# Cree_4x4__Led_Panel_V3.net
KiCad netlist of a schematic drawn in EAGLE
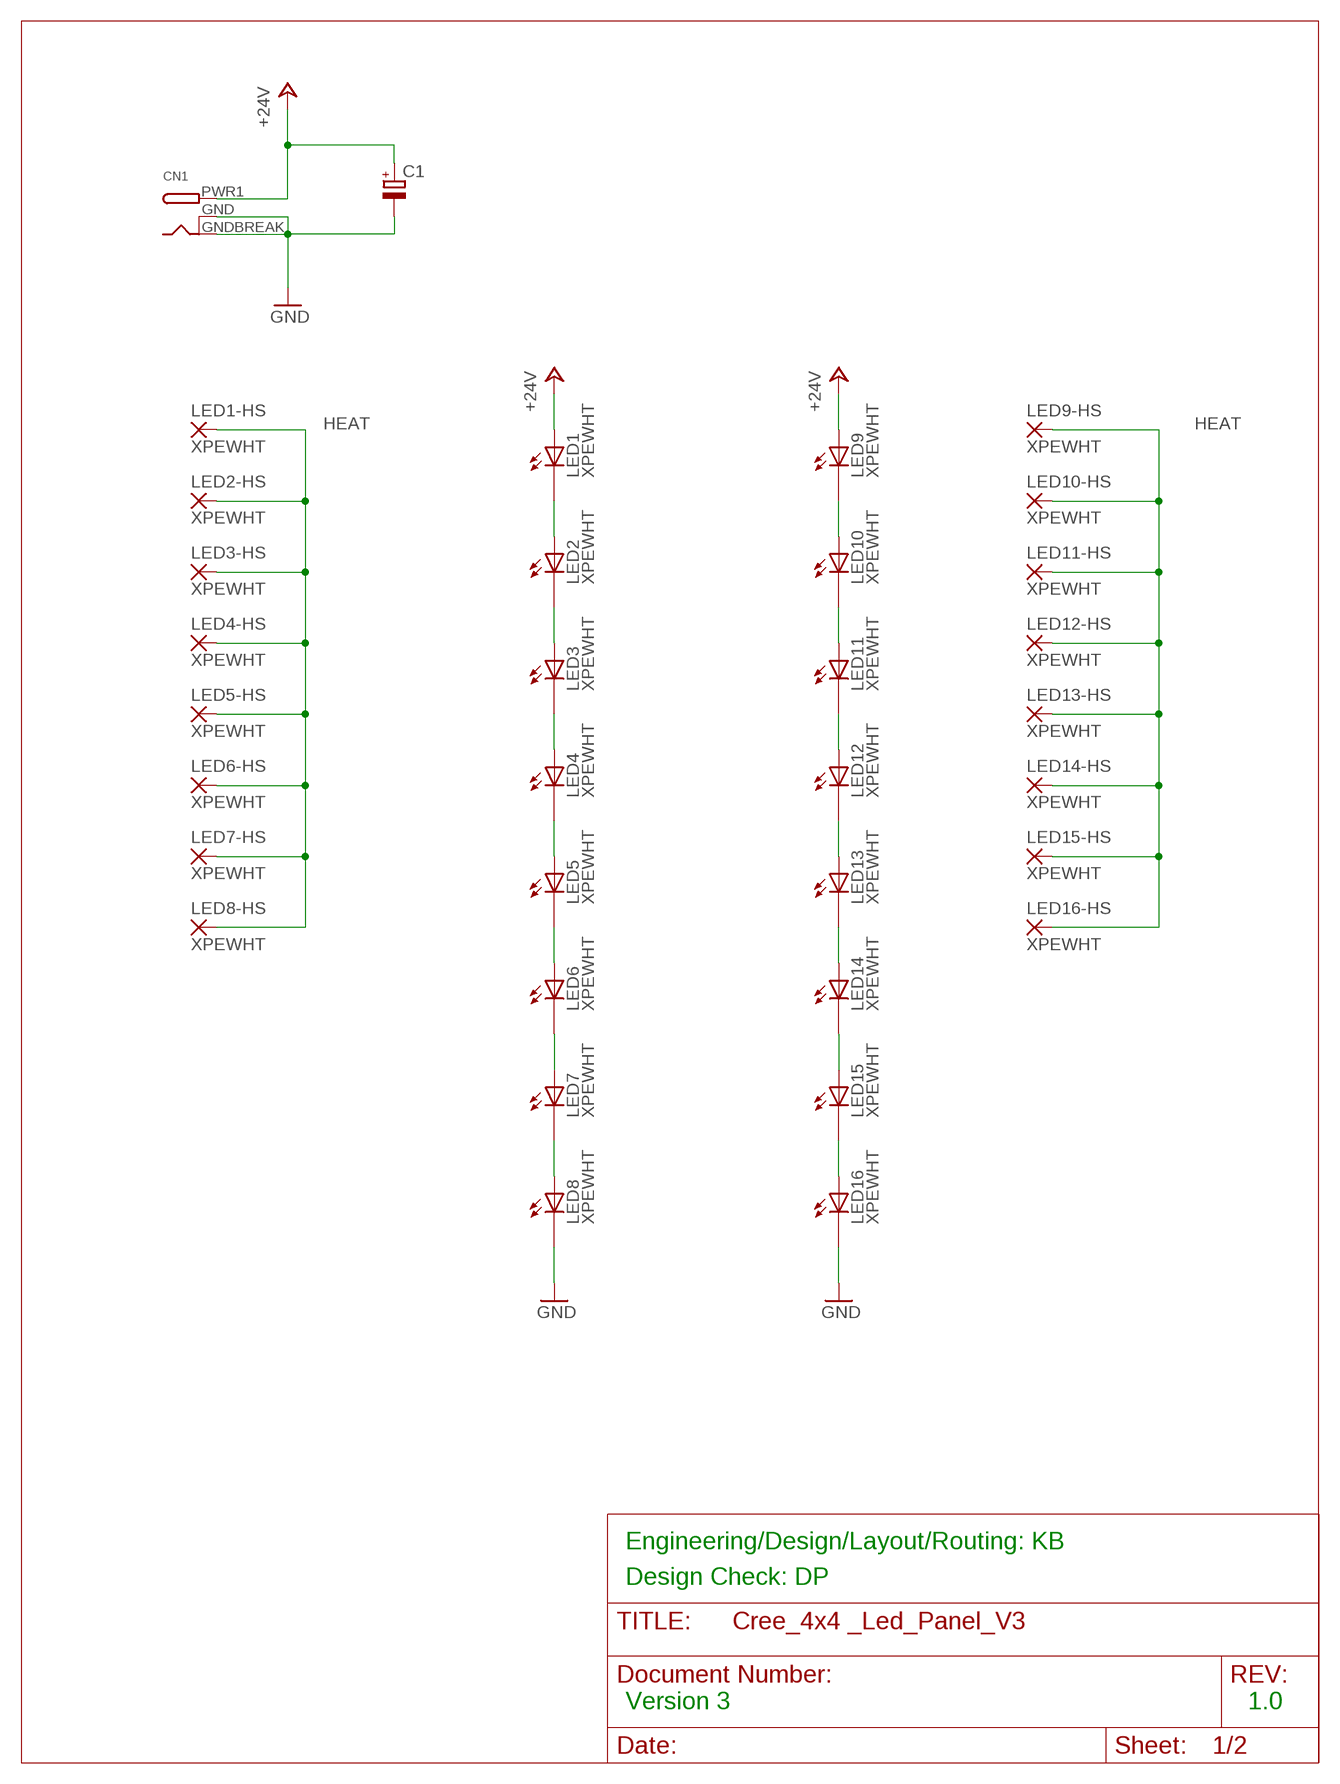
[diagram p0: schematic, sheet 1]
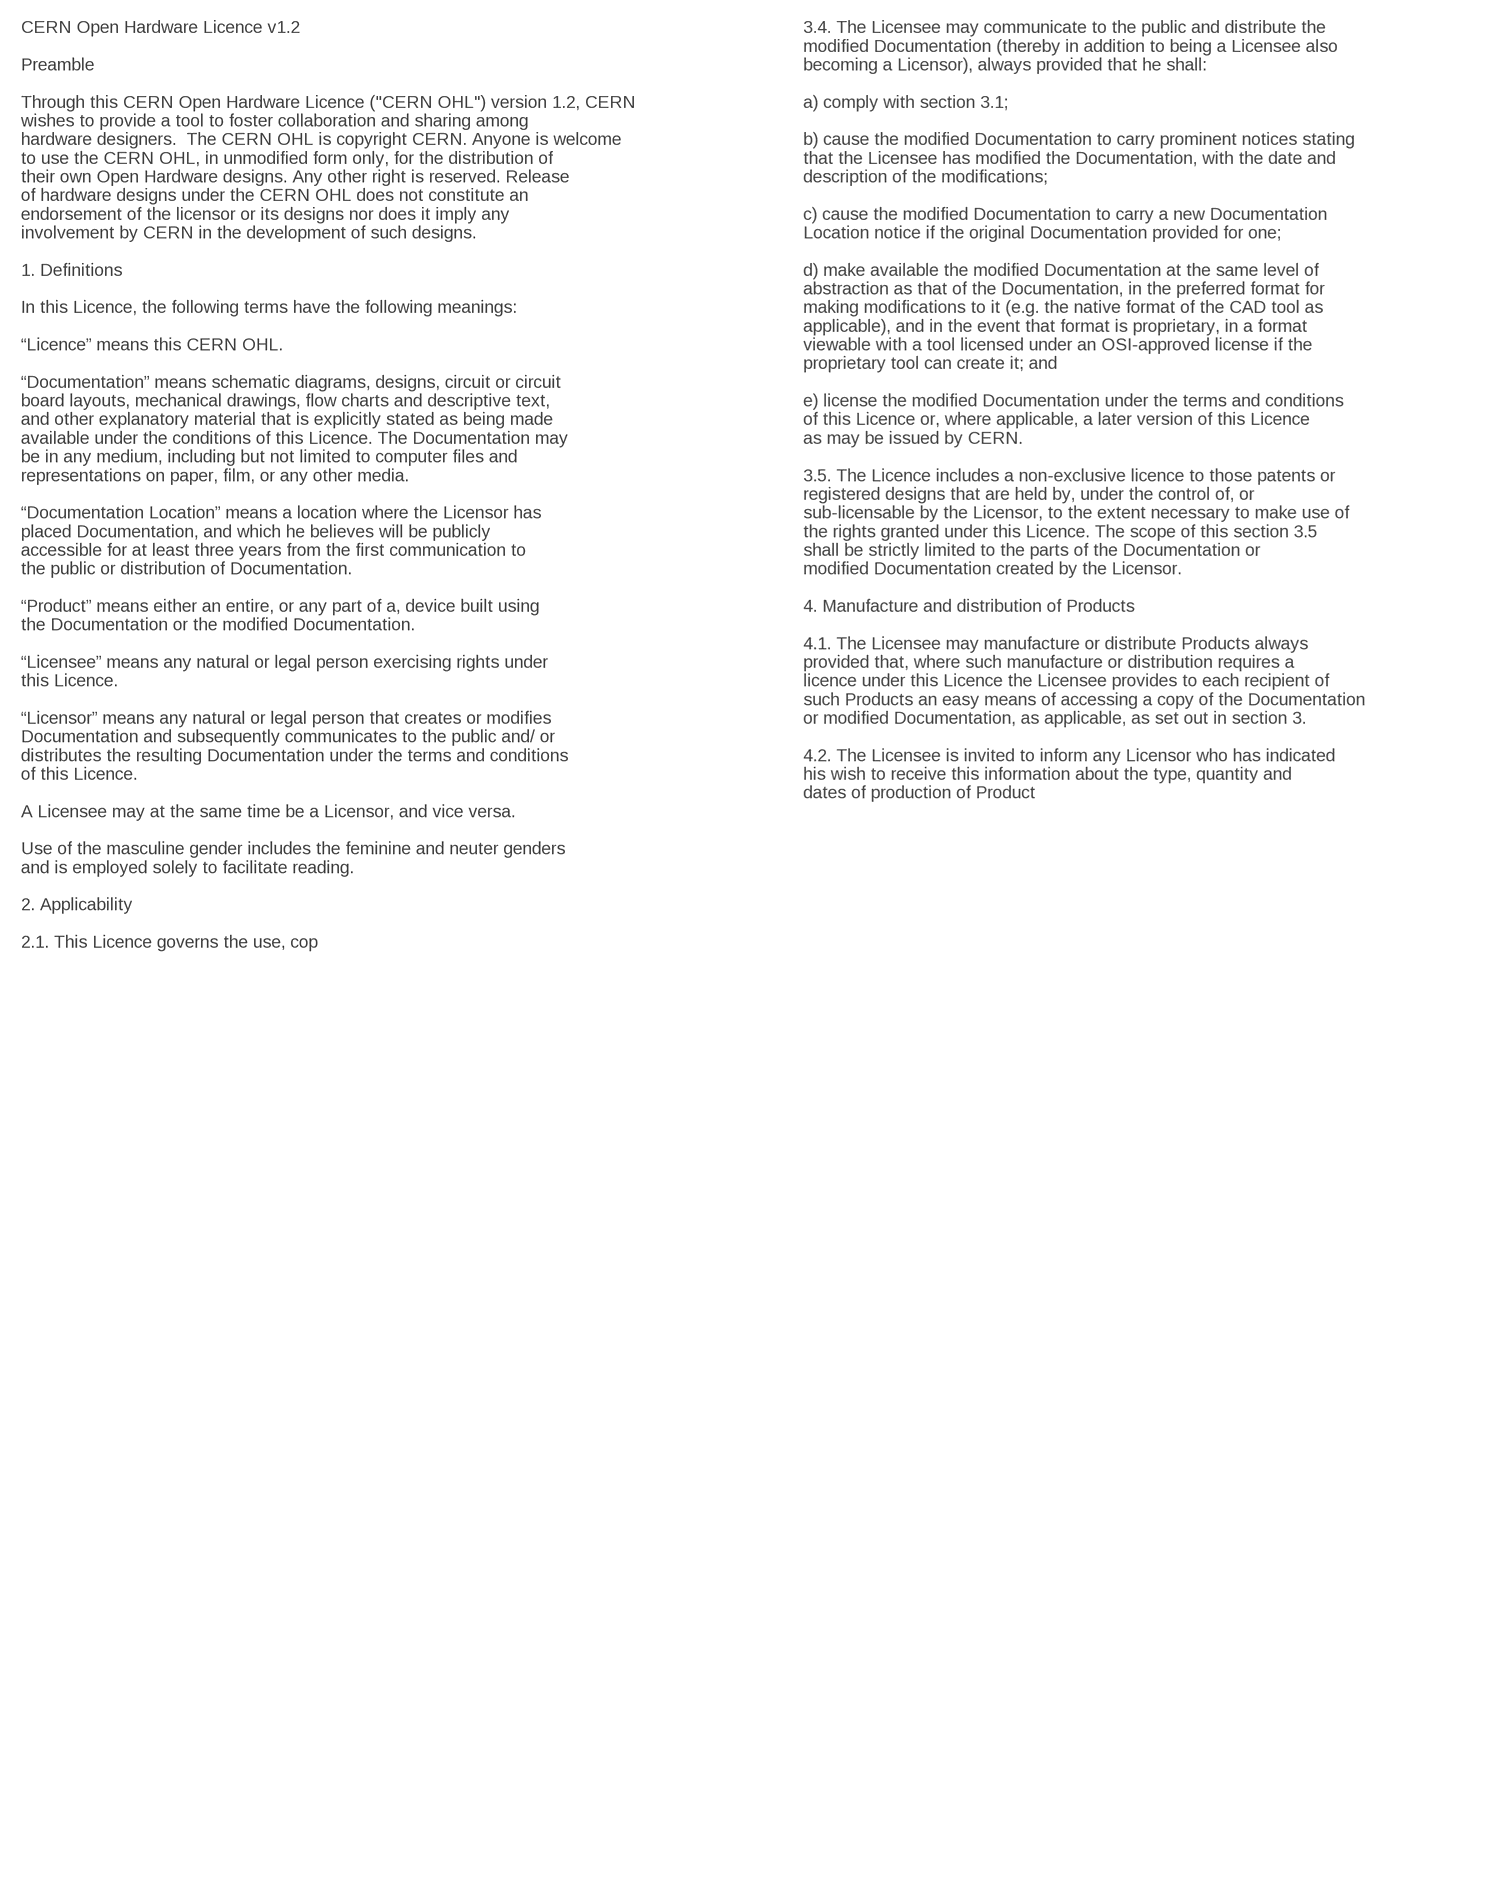
[diagram p1: schematic, sheet 2]

(export (version "E")
  (design (tool "Eeschema 10.0.6"))
  (components
    (comp (ref "C1")
      (value "CPOL-EUSMCC")
      (footprint "eagle-import:SMC_C")
      (libsource (lib "eagle-import") (part "CPOL-EUSMCC"))
    )
    (comp (ref "CN1")
      (value "DCBARRELSMT")
      (footprint "eagle-import:DCJACK_2MM_SMT")
      (libsource (lib "eagle-import") (part "DCBARRELSMT"))
    )
    (comp (ref "LED1")
      (value "XPEWHT")
      (footprint "eagle-import:CREE_XLAMP")
      (libsource (lib "eagle-import") (part "XPEWHT-01-0000-00BC2"))
    )
    (comp (ref "LED2")
      (value "XPEWHT")
      (footprint "eagle-import:CREE_XLAMP")
      (libsource (lib "eagle-import") (part "XPEWHT-01-0000-00BC2"))
    )
    (comp (ref "LED3")
      (value "XPEWHT")
      (footprint "eagle-import:CREE_XLAMP")
      (libsource (lib "eagle-import") (part "XPEWHT-01-0000-00BC2"))
    )
    (comp (ref "LED4")
      (value "XPEWHT")
      (footprint "eagle-import:CREE_XLAMP")
      (libsource (lib "eagle-import") (part "XPEWHT-01-0000-00BC2"))
    )
    (comp (ref "LED5")
      (value "XPEWHT")
      (footprint "eagle-import:CREE_XLAMP")
      (libsource (lib "eagle-import") (part "XPEWHT-01-0000-00BC2"))
    )
    (comp (ref "LED6")
      (value "XPEWHT")
      (footprint "eagle-import:CREE_XLAMP")
      (libsource (lib "eagle-import") (part "XPEWHT-01-0000-00BC2"))
    )
    (comp (ref "LED7")
      (value "XPEWHT")
      (footprint "eagle-import:CREE_XLAMP")
      (libsource (lib "eagle-import") (part "XPEWHT-01-0000-00BC2"))
    )
    (comp (ref "LED8")
      (value "XPEWHT")
      (footprint "eagle-import:CREE_XLAMP")
      (libsource (lib "eagle-import") (part "XPEWHT-01-0000-00BC2"))
    )
    (comp (ref "LED9")
      (value "XPEWHT")
      (footprint "eagle-import:CREE_XLAMP")
      (libsource (lib "eagle-import") (part "XPEWHT-01-0000-00BC2"))
    )
    (comp (ref "LED10")
      (value "XPEWHT")
      (footprint "eagle-import:CREE_XLAMP")
      (libsource (lib "eagle-import") (part "XPEWHT-01-0000-00BC2"))
    )
    (comp (ref "LED11")
      (value "XPEWHT")
      (footprint "eagle-import:CREE_XLAMP")
      (libsource (lib "eagle-import") (part "XPEWHT-01-0000-00BC2"))
    )
    (comp (ref "LED12")
      (value "XPEWHT")
      (footprint "eagle-import:CREE_XLAMP")
      (libsource (lib "eagle-import") (part "XPEWHT-01-0000-00BC2"))
    )
    (comp (ref "LED13")
      (value "XPEWHT")
      (footprint "eagle-import:CREE_XLAMP")
      (libsource (lib "eagle-import") (part "XPEWHT-01-0000-00BC2"))
    )
    (comp (ref "LED14")
      (value "XPEWHT")
      (footprint "eagle-import:CREE_XLAMP")
      (libsource (lib "eagle-import") (part "XPEWHT-01-0000-00BC2"))
    )
    (comp (ref "LED15")
      (value "XPEWHT")
      (footprint "eagle-import:CREE_XLAMP")
      (libsource (lib "eagle-import") (part "XPEWHT-01-0000-00BC2"))
    )
    (comp (ref "LED16")
      (value "XPEWHT")
      (footprint "eagle-import:CREE_XLAMP")
      (libsource (lib "eagle-import") (part "XPEWHT-01-0000-00BC2"))
    )
  )
  (nets
    (net (code "1") (name "+24V") (class "Default")
      (node (ref "C1") (pin "+") (pinfunction "+_+") (pintype "passive"))
      (node (ref "CN1") (pin "PWR1") (pinfunction "PWR_PWR1") (pintype "power_in"))
      (node (ref "LED1") (pin "A") (pinfunction "A_A") (pintype "passive"))
      (node (ref "LED9") (pin "A") (pinfunction "A_A") (pintype "passive"))
    )
    (net (code "2") (name "GND") (class "Default")
      (node (ref "C1") (pin "-") (pinfunction "-_-") (pintype "passive"))
      (node (ref "CN1") (pin "GND") (pinfunction "GNDBREAK_GND") (pintype "power_in"))
      (node (ref "CN1") (pin "GNDBREAK") (pinfunction "GND_GNDBREAK") (pintype "power_in"))
      (node (ref "LED16") (pin "C") (pinfunction "C_C") (pintype "passive"))
      (node (ref "LED8") (pin "C") (pinfunction "C_C") (pintype "passive"))
    )
    (net (code "3") (name "HEAT") (class "Default")
      (node (ref "LED1") (pin "X") (pinfunction "P_X") (pintype "passive"))
      (node (ref "LED10") (pin "X") (pinfunction "P_X") (pintype "passive"))
      (node (ref "LED11") (pin "X") (pinfunction "P_X") (pintype "passive"))
      (node (ref "LED12") (pin "X") (pinfunction "P_X") (pintype "passive"))
      (node (ref "LED13") (pin "X") (pinfunction "P_X") (pintype "passive"))
      (node (ref "LED14") (pin "X") (pinfunction "P_X") (pintype "passive"))
      (node (ref "LED15") (pin "X") (pinfunction "P_X") (pintype "passive"))
      (node (ref "LED16") (pin "X") (pinfunction "P_X") (pintype "passive"))
      (node (ref "LED2") (pin "X") (pinfunction "P_X") (pintype "passive"))
      (node (ref "LED3") (pin "X") (pinfunction "P_X") (pintype "passive"))
      (node (ref "LED4") (pin "X") (pinfunction "P_X") (pintype "passive"))
      (node (ref "LED5") (pin "X") (pinfunction "P_X") (pintype "passive"))
      (node (ref "LED6") (pin "X") (pinfunction "P_X") (pintype "passive"))
      (node (ref "LED7") (pin "X") (pinfunction "P_X") (pintype "passive"))
      (node (ref "LED8") (pin "X") (pinfunction "P_X") (pintype "passive"))
      (node (ref "LED9") (pin "X") (pinfunction "P_X") (pintype "passive"))
    )
    (net (code "4") (name "Net-(LED1-PadC)") (class "Default")
      (node (ref "LED1") (pin "C") (pinfunction "C_C") (pintype "passive"))
      (node (ref "LED2") (pin "A") (pinfunction "A_A") (pintype "passive"))
    )
    (net (code "5") (name "Net-(LED2-PadC)") (class "Default")
      (node (ref "LED2") (pin "C") (pinfunction "C_C") (pintype "passive"))
      (node (ref "LED3") (pin "A") (pinfunction "A_A") (pintype "passive"))
    )
    (net (code "6") (name "Net-(LED3-PadC)") (class "Default")
      (node (ref "LED3") (pin "C") (pinfunction "C_C") (pintype "passive"))
      (node (ref "LED4") (pin "A") (pinfunction "A_A") (pintype "passive"))
    )
    (net (code "7") (name "Net-(LED4-PadC)") (class "Default")
      (node (ref "LED4") (pin "C") (pinfunction "C_C") (pintype "passive"))
      (node (ref "LED5") (pin "A") (pinfunction "A_A") (pintype "passive"))
    )
    (net (code "8") (name "Net-(LED5-PadC)") (class "Default")
      (node (ref "LED5") (pin "C") (pinfunction "C_C") (pintype "passive"))
      (node (ref "LED6") (pin "A") (pinfunction "A_A") (pintype "passive"))
    )
    (net (code "9") (name "Net-(LED6-PadC)") (class "Default")
      (node (ref "LED6") (pin "C") (pinfunction "C_C") (pintype "passive"))
      (node (ref "LED7") (pin "A") (pinfunction "A_A") (pintype "passive"))
    )
    (net (code "10") (name "Net-(LED7-PadC)") (class "Default")
      (node (ref "LED7") (pin "C") (pinfunction "C_C") (pintype "passive"))
      (node (ref "LED8") (pin "A") (pinfunction "A_A") (pintype "passive"))
    )
    (net (code "11") (name "Net-(LED10-PadA)") (class "Default")
      (node (ref "LED10") (pin "A") (pinfunction "A_A") (pintype "passive"))
      (node (ref "LED9") (pin "C") (pinfunction "C_C") (pintype "passive"))
    )
    (net (code "12") (name "Net-(LED10-PadC)") (class "Default")
      (node (ref "LED10") (pin "C") (pinfunction "C_C") (pintype "passive"))
      (node (ref "LED11") (pin "A") (pinfunction "A_A") (pintype "passive"))
    )
    (net (code "13") (name "Net-(LED11-PadC)") (class "Default")
      (node (ref "LED11") (pin "C") (pinfunction "C_C") (pintype "passive"))
      (node (ref "LED12") (pin "A") (pinfunction "A_A") (pintype "passive"))
    )
    (net (code "14") (name "Net-(LED12-PadC)") (class "Default")
      (node (ref "LED12") (pin "C") (pinfunction "C_C") (pintype "passive"))
      (node (ref "LED13") (pin "A") (pinfunction "A_A") (pintype "passive"))
    )
    (net (code "15") (name "Net-(LED13-PadC)") (class "Default")
      (node (ref "LED13") (pin "C") (pinfunction "C_C") (pintype "passive"))
      (node (ref "LED14") (pin "A") (pinfunction "A_A") (pintype "passive"))
    )
    (net (code "16") (name "Net-(LED14-PadC)") (class "Default")
      (node (ref "LED14") (pin "C") (pinfunction "C_C") (pintype "passive"))
      (node (ref "LED15") (pin "A") (pinfunction "A_A") (pintype "passive"))
    )
    (net (code "17") (name "Net-(LED15-PadC)") (class "Default")
      (node (ref "LED15") (pin "C") (pinfunction "C_C") (pintype "passive"))
      (node (ref "LED16") (pin "A") (pinfunction "A_A") (pintype "passive"))
    )
    (net (code "18") (name "unconnected-(LED1B-A-PadA@1)") (class "Default")
      (node (ref "LED1") (pin "A@1") (pinfunction "A_A@1") (pintype "passive"))
    )
    (net (code "19") (name "unconnected-(LED1B-C-PadC@1)") (class "Default")
      (node (ref "LED1") (pin "C@1") (pinfunction "C_C@1") (pintype "passive"))
    )
    (net (code "20") (name "unconnected-(LED2B-A-PadA@1)") (class "Default")
      (node (ref "LED2") (pin "A@1") (pinfunction "A_A@1") (pintype "passive"))
    )
    (net (code "21") (name "unconnected-(LED2B-C-PadC@1)") (class "Default")
      (node (ref "LED2") (pin "C@1") (pinfunction "C_C@1") (pintype "passive"))
    )
    (net (code "22") (name "unconnected-(LED3B-A-PadA@1)") (class "Default")
      (node (ref "LED3") (pin "A@1") (pinfunction "A_A@1") (pintype "passive"))
    )
    (net (code "23") (name "unconnected-(LED3B-C-PadC@1)") (class "Default")
      (node (ref "LED3") (pin "C@1") (pinfunction "C_C@1") (pintype "passive"))
    )
    (net (code "24") (name "unconnected-(LED4B-A-PadA@1)") (class "Default")
      (node (ref "LED4") (pin "A@1") (pinfunction "A_A@1") (pintype "passive"))
    )
    (net (code "25") (name "unconnected-(LED4B-C-PadC@1)") (class "Default")
      (node (ref "LED4") (pin "C@1") (pinfunction "C_C@1") (pintype "passive"))
    )
    (net (code "26") (name "unconnected-(LED5B-A-PadA@1)") (class "Default")
      (node (ref "LED5") (pin "A@1") (pinfunction "A_A@1") (pintype "passive"))
    )
    (net (code "27") (name "unconnected-(LED5B-C-PadC@1)") (class "Default")
      (node (ref "LED5") (pin "C@1") (pinfunction "C_C@1") (pintype "passive"))
    )
    (net (code "28") (name "unconnected-(LED6B-A-PadA@1)") (class "Default")
      (node (ref "LED6") (pin "A@1") (pinfunction "A_A@1") (pintype "passive"))
    )
    (net (code "29") (name "unconnected-(LED6B-C-PadC@1)") (class "Default")
      (node (ref "LED6") (pin "C@1") (pinfunction "C_C@1") (pintype "passive"))
    )
    (net (code "30") (name "unconnected-(LED7B-A-PadA@1)") (class "Default")
      (node (ref "LED7") (pin "A@1") (pinfunction "A_A@1") (pintype "passive"))
    )
    (net (code "31") (name "unconnected-(LED7B-C-PadC@1)") (class "Default")
      (node (ref "LED7") (pin "C@1") (pinfunction "C_C@1") (pintype "passive"))
    )
    (net (code "32") (name "unconnected-(LED8B-A-PadA@1)") (class "Default")
      (node (ref "LED8") (pin "A@1") (pinfunction "A_A@1") (pintype "passive"))
    )
    (net (code "33") (name "unconnected-(LED8B-C-PadC@1)") (class "Default")
      (node (ref "LED8") (pin "C@1") (pinfunction "C_C@1") (pintype "passive"))
    )
    (net (code "34") (name "unconnected-(LED9B-A-PadA@1)") (class "Default")
      (node (ref "LED9") (pin "A@1") (pinfunction "A_A@1") (pintype "passive"))
    )
    (net (code "35") (name "unconnected-(LED9B-C-PadC@1)") (class "Default")
      (node (ref "LED9") (pin "C@1") (pinfunction "C_C@1") (pintype "passive"))
    )
    (net (code "36") (name "unconnected-(LED10B-A-PadA@1)") (class "Default")
      (node (ref "LED10") (pin "A@1") (pinfunction "A_A@1") (pintype "passive"))
    )
    (net (code "37") (name "unconnected-(LED10B-C-PadC@1)") (class "Default")
      (node (ref "LED10") (pin "C@1") (pinfunction "C_C@1") (pintype "passive"))
    )
    (net (code "38") (name "unconnected-(LED11B-A-PadA@1)") (class "Default")
      (node (ref "LED11") (pin "A@1") (pinfunction "A_A@1") (pintype "passive"))
    )
    (net (code "39") (name "unconnected-(LED11B-C-PadC@1)") (class "Default")
      (node (ref "LED11") (pin "C@1") (pinfunction "C_C@1") (pintype "passive"))
    )
    (net (code "40") (name "unconnected-(LED12B-A-PadA@1)") (class "Default")
      (node (ref "LED12") (pin "A@1") (pinfunction "A_A@1") (pintype "passive"))
    )
    (net (code "41") (name "unconnected-(LED12B-C-PadC@1)") (class "Default")
      (node (ref "LED12") (pin "C@1") (pinfunction "C_C@1") (pintype "passive"))
    )
    (net (code "42") (name "unconnected-(LED13B-A-PadA@1)") (class "Default")
      (node (ref "LED13") (pin "A@1") (pinfunction "A_A@1") (pintype "passive"))
    )
    (net (code "43") (name "unconnected-(LED13B-C-PadC@1)") (class "Default")
      (node (ref "LED13") (pin "C@1") (pinfunction "C_C@1") (pintype "passive"))
    )
    (net (code "44") (name "unconnected-(LED14B-A-PadA@1)") (class "Default")
      (node (ref "LED14") (pin "A@1") (pinfunction "A_A@1") (pintype "passive"))
    )
    (net (code "45") (name "unconnected-(LED14B-C-PadC@1)") (class "Default")
      (node (ref "LED14") (pin "C@1") (pinfunction "C_C@1") (pintype "passive"))
    )
    (net (code "46") (name "unconnected-(LED15B-A-PadA@1)") (class "Default")
      (node (ref "LED15") (pin "A@1") (pinfunction "A_A@1") (pintype "passive"))
    )
    (net (code "47") (name "unconnected-(LED15B-C-PadC@1)") (class "Default")
      (node (ref "LED15") (pin "C@1") (pinfunction "C_C@1") (pintype "passive"))
    )
    (net (code "48") (name "unconnected-(LED16B-A-PadA@1)") (class "Default")
      (node (ref "LED16") (pin "A@1") (pinfunction "A_A@1") (pintype "passive"))
    )
    (net (code "49") (name "unconnected-(LED16B-C-PadC@1)") (class "Default")
      (node (ref "LED16") (pin "C@1") (pinfunction "C_C@1") (pintype "passive"))
    )
  )
)
